# ioboard.net
KiCad netlist of a schematic drawn in EAGLE
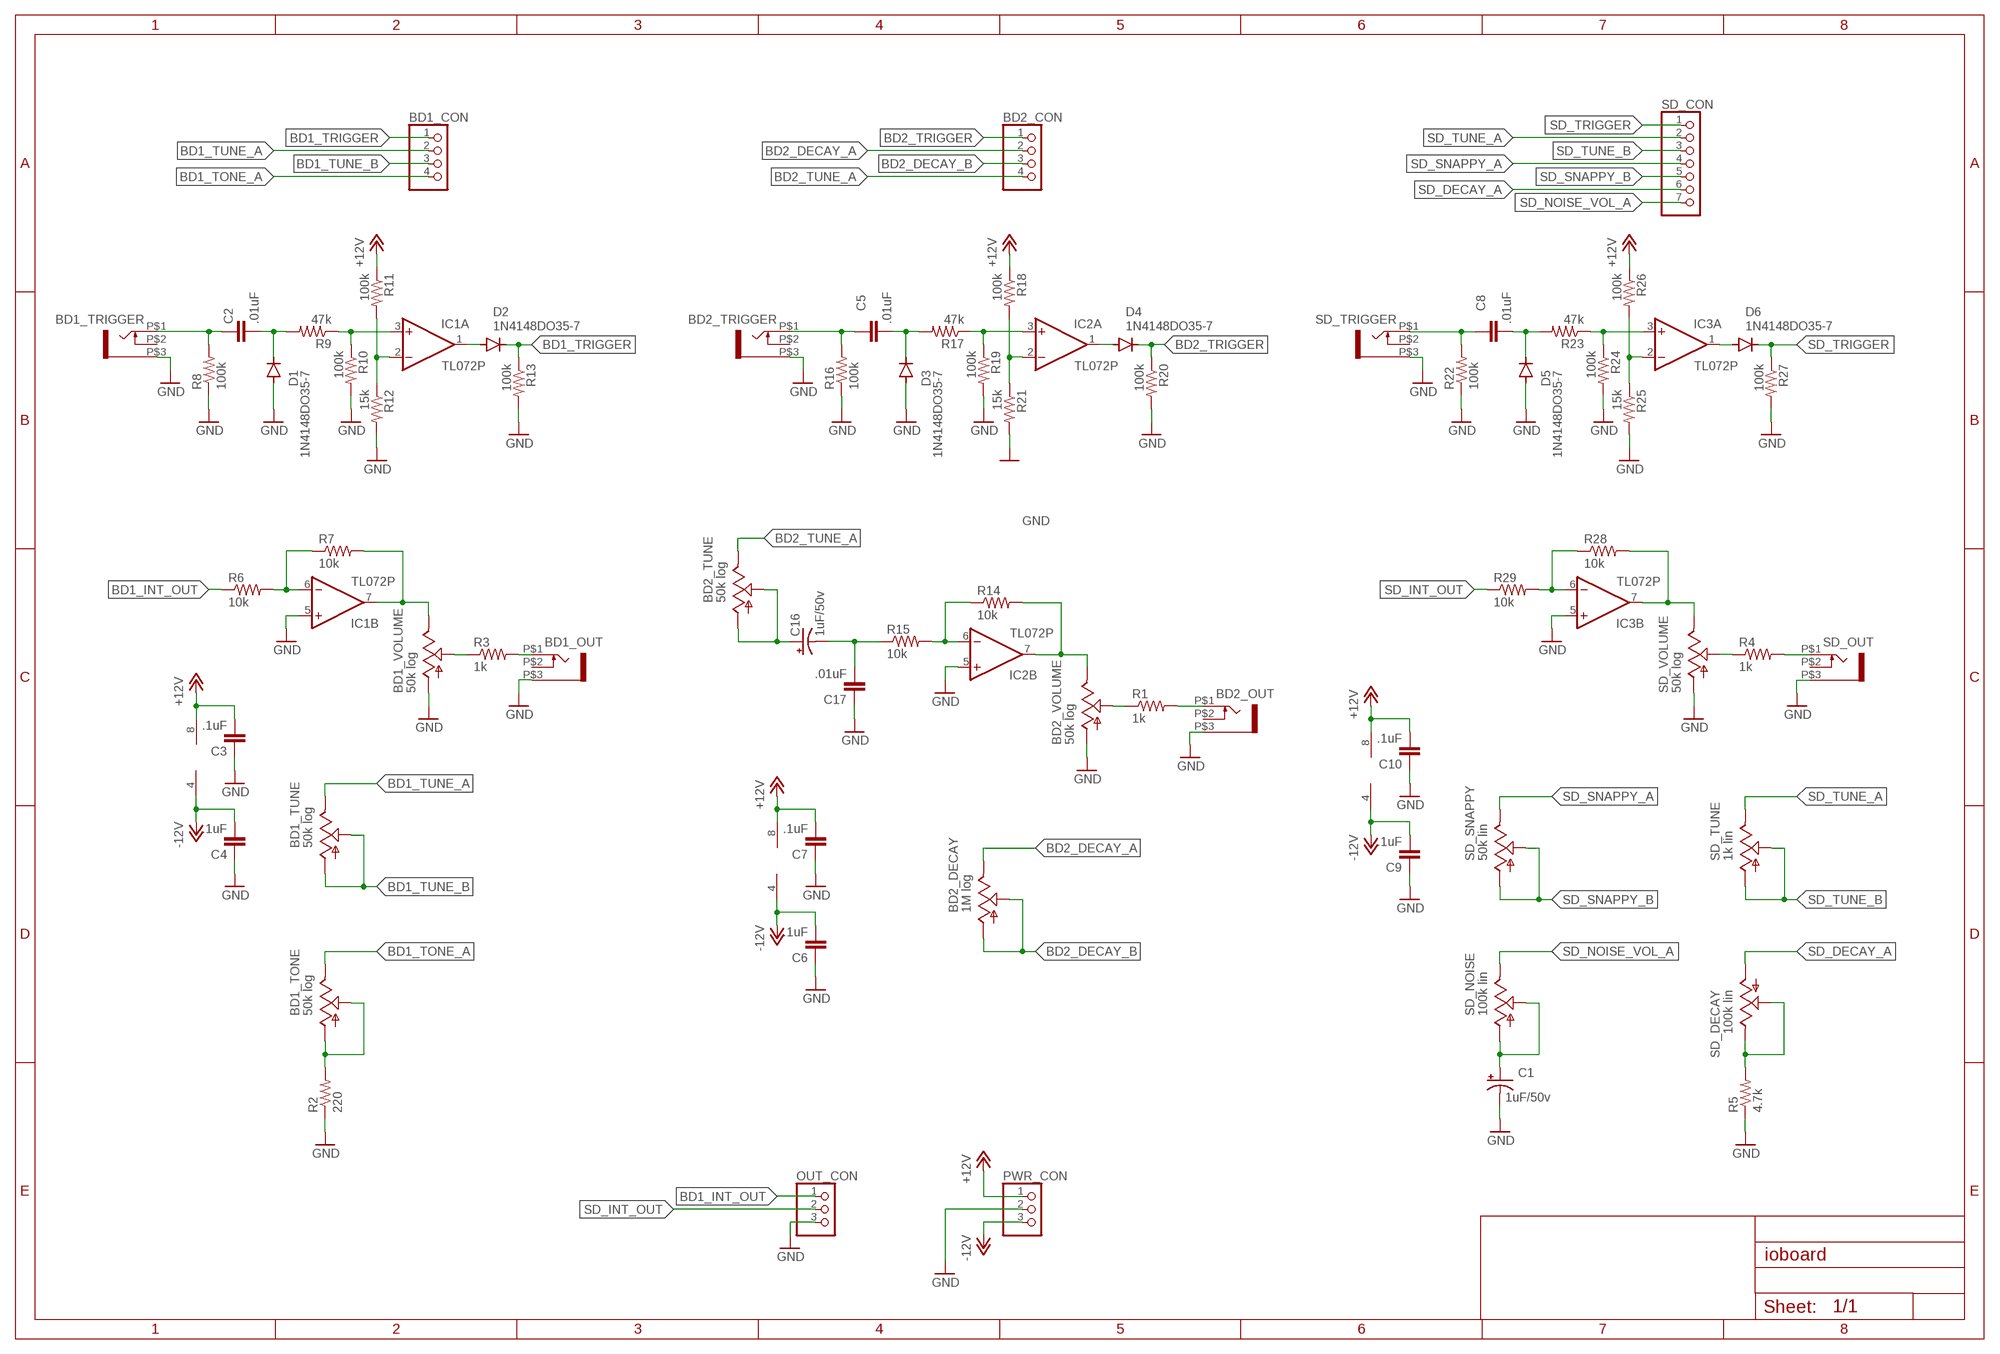
[diagram p0: schematic, sheet 1]

(export (version "E")
  (design (tool "Eeschema 10.0.6"))
  (components
    (comp (ref "BD1_CON")
      (value "PINHD-1X4")
      (footprint "eagle-import:1X04")
      (libsource (lib "eagle-import") (part "PINHD-1X4"))
    )
    (comp (ref "BD1_OUT")
      (value "WQP-PJ301M-12_JACK")
      (footprint "eagle-import:WQP-PJ301M-12_JACK")
      (libsource (lib "eagle-import") (part "WQP-PJ301M-12_JACK"))
    )
    (comp (ref "BD1_TONE")
      (value "50k log")
      (footprint "eagle-import:EVUF")
      (libsource (lib "eagle-import") (part "ALPHA-9MMA"))
    )
    (comp (ref "BD1_TRIGGER")
      (value "WQP-PJ301M-12_JACK")
      (footprint "eagle-import:WQP-PJ301M-12_JACK")
      (libsource (lib "eagle-import") (part "WQP-PJ301M-12_JACK"))
    )
    (comp (ref "BD1_TUNE")
      (value "50k log")
      (footprint "eagle-import:EVUF")
      (libsource (lib "eagle-import") (part "ALPHA-9MMA"))
    )
    (comp (ref "BD1_VOLUME")
      (value "50k log")
      (footprint "eagle-import:EVUF")
      (libsource (lib "eagle-import") (part "ALPHA-9MMA"))
    )
    (comp (ref "BD2_CON")
      (value "PINHD-1X4")
      (footprint "eagle-import:1X04")
      (libsource (lib "eagle-import") (part "PINHD-1X4"))
    )
    (comp (ref "BD2_DECAY")
      (value "1M log")
      (footprint "eagle-import:EVUF")
      (libsource (lib "eagle-import") (part "ALPHA-9MMA"))
    )
    (comp (ref "BD2_OUT")
      (value "WQP-PJ301M-12_JACK")
      (footprint "eagle-import:WQP-PJ301M-12_JACK")
      (libsource (lib "eagle-import") (part "WQP-PJ301M-12_JACK"))
    )
    (comp (ref "BD2_TRIGGER")
      (value "WQP-PJ301M-12_JACK")
      (footprint "eagle-import:WQP-PJ301M-12_JACK")
      (libsource (lib "eagle-import") (part "WQP-PJ301M-12_JACK"))
    )
    (comp (ref "BD2_TUNE")
      (value "50k log")
      (footprint "eagle-import:EVUF")
      (libsource (lib "eagle-import") (part "ALPHA-9MMA"))
    )
    (comp (ref "BD2_VOLUME")
      (value "50k log")
      (footprint "eagle-import:EVUF")
      (libsource (lib "eagle-import") (part "ALPHA-9MMA"))
    )
    (comp (ref "C1")
      (value "1uF/50v")
      (footprint "eagle-import:E2,5-5")
      (libsource (lib "eagle-import") (part "CPOL-USE2.5-5"))
    )
    (comp (ref "C2")
      (value ".01uF")
      (footprint "eagle-import:C050-024X044")
      (libsource (lib "eagle-import") (part "C-EU050-024X044"))
    )
    (comp (ref "C3")
      (value ".1uF")
      (footprint "eagle-import:C050-024X044")
      (libsource (lib "eagle-import") (part "C-EU050-024X044"))
    )
    (comp (ref "C4")
      (value ".1uF")
      (footprint "eagle-import:C050-024X044")
      (libsource (lib "eagle-import") (part "C-EU050-024X044"))
    )
    (comp (ref "C5")
      (value ".01uF")
      (footprint "eagle-import:C050-024X044")
      (libsource (lib "eagle-import") (part "C-EU050-024X044"))
    )
    (comp (ref "C6")
      (value ".1uF")
      (footprint "eagle-import:C050-024X044")
      (libsource (lib "eagle-import") (part "C-EU050-024X044"))
    )
    (comp (ref "C7")
      (value ".1uF")
      (footprint "eagle-import:C050-024X044")
      (libsource (lib "eagle-import") (part "C-EU050-024X044"))
    )
    (comp (ref "C8")
      (value ".01uF")
      (footprint "eagle-import:C050-024X044")
      (libsource (lib "eagle-import") (part "C-EU050-024X044"))
    )
    (comp (ref "C9")
      (value ".1uF")
      (footprint "eagle-import:C050-024X044")
      (libsource (lib "eagle-import") (part "C-EU050-024X044"))
    )
    (comp (ref "C10")
      (value ".1uF")
      (footprint "eagle-import:C050-024X044")
      (libsource (lib "eagle-import") (part "C-EU050-024X044"))
    )
    (comp (ref "C16")
      (value "1uF/50v")
      (footprint "eagle-import:E2,5-6")
      (libsource (lib "eagle-import") (part "CPOL-USE2.5-6"))
    )
    (comp (ref "C17")
      (value ".01uF")
      (footprint "eagle-import:C050-024X044")
      (libsource (lib "eagle-import") (part "resistor_C-EU050-024X044"))
    )
    (comp (ref "D1")
      (value "1N4148DO35-7")
      (footprint "eagle-import:DO35-7")
      (libsource (lib "eagle-import") (part "1N4148DO35-7"))
    )
    (comp (ref "D2")
      (value "1N4148DO35-7")
      (footprint "eagle-import:DO35-7")
      (libsource (lib "eagle-import") (part "1N4148DO35-7"))
    )
    (comp (ref "D3")
      (value "1N4148DO35-7")
      (footprint "eagle-import:DO35-7")
      (libsource (lib "eagle-import") (part "1N4148DO35-7"))
    )
    (comp (ref "D4")
      (value "1N4148DO35-7")
      (footprint "eagle-import:DO35-7")
      (libsource (lib "eagle-import") (part "1N4148DO35-7"))
    )
    (comp (ref "D5")
      (value "1N4148DO35-7")
      (footprint "eagle-import:DO35-7")
      (libsource (lib "eagle-import") (part "1N4148DO35-7"))
    )
    (comp (ref "D6")
      (value "1N4148DO35-7")
      (footprint "eagle-import:DO35-7")
      (libsource (lib "eagle-import") (part "1N4148DO35-7"))
    )
    (comp (ref "IC1")
      (value "TL072P")
      (footprint "eagle-import:DIL08")
      (libsource (lib "eagle-import") (part "TL072P"))
    )
    (comp (ref "IC2")
      (value "TL072P")
      (footprint "eagle-import:DIL08")
      (libsource (lib "eagle-import") (part "TL072P"))
    )
    (comp (ref "IC3")
      (value "TL072P")
      (footprint "eagle-import:DIL08")
      (libsource (lib "eagle-import") (part "TL072P"))
    )
    (comp (ref "OUT_CON")
      (value "PINHD-1X3")
      (footprint "eagle-import:1X03")
      (libsource (lib "eagle-import") (part "PINHD-1X3"))
    )
    (comp (ref "PWR_CON")
      (value "PINHD-1X3")
      (footprint "eagle-import:1X03")
      (libsource (lib "eagle-import") (part "PINHD-1X3"))
    )
    (comp (ref "R1")
      (value "1k")
      (footprint "eagle-import:0207_7")
      (libsource (lib "eagle-import") (part "R-US_0207/7"))
    )
    (comp (ref "R2")
      (value "220")
      (footprint "eagle-import:0207_7")
      (libsource (lib "eagle-import") (part "R-US_0207/7"))
    )
    (comp (ref "R3")
      (value "1k")
      (footprint "eagle-import:0207_7")
      (libsource (lib "eagle-import") (part "R-US_0207/7"))
    )
    (comp (ref "R4")
      (value "1k")
      (footprint "eagle-import:0207_7")
      (libsource (lib "eagle-import") (part "R-US_0207/7"))
    )
    (comp (ref "R5")
      (value "4.7k")
      (footprint "eagle-import:0207_7")
      (libsource (lib "eagle-import") (part "R-US_0207/7"))
    )
    (comp (ref "R6")
      (value "10k")
      (footprint "eagle-import:0207_7")
      (libsource (lib "eagle-import") (part "R-US_0207/7"))
    )
    (comp (ref "R7")
      (value "10k")
      (footprint "eagle-import:0207_7")
      (libsource (lib "eagle-import") (part "R-US_0207/7"))
    )
    (comp (ref "R8")
      (value "100k")
      (footprint "eagle-import:0207_7")
      (libsource (lib "eagle-import") (part "R-US_0207/7"))
    )
    (comp (ref "R9")
      (value "47k")
      (footprint "eagle-import:0207_7")
      (libsource (lib "eagle-import") (part "R-US_0207/7"))
    )
    (comp (ref "R10")
      (value "100k")
      (footprint "eagle-import:0207_7")
      (libsource (lib "eagle-import") (part "R-US_0207/7"))
    )
    (comp (ref "R11")
      (value "100k")
      (footprint "eagle-import:0207_7")
      (libsource (lib "eagle-import") (part "R-US_0207/7"))
    )
    (comp (ref "R12")
      (value "15k")
      (footprint "eagle-import:0207_7")
      (libsource (lib "eagle-import") (part "R-US_0207/7"))
    )
    (comp (ref "R13")
      (value "100k")
      (footprint "eagle-import:0207_7")
      (libsource (lib "eagle-import") (part "R-US_0207/7"))
    )
    (comp (ref "R14")
      (value "10k")
      (footprint "eagle-import:0207_7")
      (libsource (lib "eagle-import") (part "R-US_0207/7"))
    )
    (comp (ref "R15")
      (value "10k")
      (footprint "eagle-import:0207_7")
      (libsource (lib "eagle-import") (part "R-US_0207/7"))
    )
    (comp (ref "R16")
      (value "100k")
      (footprint "eagle-import:0207_7")
      (libsource (lib "eagle-import") (part "R-US_0207/7"))
    )
    (comp (ref "R17")
      (value "47k")
      (footprint "eagle-import:0207_7")
      (libsource (lib "eagle-import") (part "R-US_0207/7"))
    )
    (comp (ref "R18")
      (value "100k")
      (footprint "eagle-import:0207_7")
      (libsource (lib "eagle-import") (part "R-US_0207/7"))
    )
    (comp (ref "R19")
      (value "100k")
      (footprint "eagle-import:0207_7")
      (libsource (lib "eagle-import") (part "R-US_0207/7"))
    )
    (comp (ref "R20")
      (value "100k")
      (footprint "eagle-import:0207_7")
      (libsource (lib "eagle-import") (part "R-US_0207/7"))
    )
    (comp (ref "R21")
      (value "15k")
      (footprint "eagle-import:0207_7")
      (libsource (lib "eagle-import") (part "R-US_0207/7"))
    )
    (comp (ref "R22")
      (value "100k")
      (footprint "eagle-import:0207_7")
      (libsource (lib "eagle-import") (part "R-US_0207/7"))
    )
    (comp (ref "R23")
      (value "47k")
      (footprint "eagle-import:0207_7")
      (libsource (lib "eagle-import") (part "R-US_0207/7"))
    )
    (comp (ref "R24")
      (value "100k")
      (footprint "eagle-import:0207_7")
      (libsource (lib "eagle-import") (part "R-US_0207/7"))
    )
    (comp (ref "R25")
      (value "15k")
      (footprint "eagle-import:0207_7")
      (libsource (lib "eagle-import") (part "R-US_0207/7"))
    )
    (comp (ref "R26")
      (value "100k")
      (footprint "eagle-import:0207_7")
      (libsource (lib "eagle-import") (part "R-US_0207/7"))
    )
    (comp (ref "R27")
      (value "100k")
      (footprint "eagle-import:0207_7")
      (libsource (lib "eagle-import") (part "R-US_0207/7"))
    )
    (comp (ref "R28")
      (value "10k")
      (footprint "eagle-import:0207_7")
      (libsource (lib "eagle-import") (part "R-US_0207/7"))
    )
    (comp (ref "R29")
      (value "10k")
      (footprint "eagle-import:0207_7")
      (libsource (lib "eagle-import") (part "R-US_0207/7"))
    )
    (comp (ref "SD_CON")
      (value "PINHD-1X7")
      (footprint "eagle-import:1X07")
      (libsource (lib "eagle-import") (part "PINHD-1X7"))
    )
    (comp (ref "SD_DECAY")
      (value "100k lin")
      (footprint "eagle-import:EVUF")
      (libsource (lib "eagle-import") (part "ALPHA-9MMA"))
    )
    (comp (ref "SD_NOISE")
      (value "100k lin")
      (footprint "eagle-import:EVUF")
      (libsource (lib "eagle-import") (part "ALPHA-9MMA"))
    )
    (comp (ref "SD_OUT")
      (value "WQP-PJ301M-12_JACK")
      (footprint "eagle-import:WQP-PJ301M-12_JACK")
      (libsource (lib "eagle-import") (part "WQP-PJ301M-12_JACK"))
    )
    (comp (ref "SD_SNAPPY")
      (value "50k lin")
      (footprint "eagle-import:EVUF")
      (libsource (lib "eagle-import") (part "ALPHA-9MMA"))
    )
    (comp (ref "SD_TRIGGER")
      (value "WQP-PJ301M-12_JACK")
      (footprint "eagle-import:WQP-PJ301M-12_JACK")
      (libsource (lib "eagle-import") (part "WQP-PJ301M-12_JACK"))
    )
    (comp (ref "SD_TUNE")
      (value "1k lin")
      (footprint "eagle-import:EVUF")
      (libsource (lib "eagle-import") (part "ALPHA-9MMA"))
    )
    (comp (ref "SD_VOLUME")
      (value "50k log")
      (footprint "eagle-import:EVUF")
      (libsource (lib "eagle-import") (part "ALPHA-9MMA"))
    )
  )
  (nets
    (net (code "1") (name "+12V") (class "Default")
      (node (ref "C10") (pin "2") (pinfunction "2_2") (pintype "passive"))
      (node (ref "C3") (pin "2") (pinfunction "2_2") (pintype "passive"))
      (node (ref "C7") (pin "2") (pinfunction "2_2") (pintype "passive"))
      (node (ref "IC1") (pin "8") (pinfunction "V+_8") (pintype "power_in"))
      (node (ref "IC2") (pin "8") (pinfunction "V+_8") (pintype "power_in"))
      (node (ref "IC3") (pin "8") (pinfunction "V+_8") (pintype "power_in"))
      (node (ref "PWR_CON") (pin "1") (pinfunction "1_1") (pintype "passive"))
      (node (ref "R11") (pin "1") (pinfunction "1_1") (pintype "passive"))
      (node (ref "R18") (pin "1") (pinfunction "1_1") (pintype "passive"))
      (node (ref "R26") (pin "1") (pinfunction "1_1") (pintype "passive"))
    )
    (net (code "2") (name "-12V") (class "Default")
      (node (ref "C4") (pin "2") (pinfunction "2_2") (pintype "passive"))
      (node (ref "C6") (pin "2") (pinfunction "2_2") (pintype "passive"))
      (node (ref "C9") (pin "2") (pinfunction "2_2") (pintype "passive"))
      (node (ref "IC1") (pin "4") (pinfunction "V-_4") (pintype "power_in"))
      (node (ref "IC2") (pin "4") (pinfunction "V-_4") (pintype "power_in"))
      (node (ref "IC3") (pin "4") (pinfunction "V-_4") (pintype "power_in"))
      (node (ref "PWR_CON") (pin "3") (pinfunction "3_3") (pintype "passive"))
    )
    (net (code "3") (name "BD1_INT_OUT") (class "Default")
      (node (ref "OUT_CON") (pin "1") (pinfunction "1_1") (pintype "passive"))
      (node (ref "R6") (pin "1") (pinfunction "1_1") (pintype "passive"))
    )
    (net (code "4") (name "BD1_TONE_A") (class "Default")
      (node (ref "BD1_CON") (pin "4") (pinfunction "4_4") (pintype "passive"))
      (node (ref "BD1_TONE") (pin "3") (pinfunction "E_3") (pintype "passive"))
    )
    (net (code "5") (name "BD1_TRIGGER") (class "Default")
      (node (ref "BD1_CON") (pin "1") (pinfunction "1_1") (pintype "passive"))
      (node (ref "D2") (pin "C") (pinfunction "C_C") (pintype "passive"))
      (node (ref "R13") (pin "1") (pinfunction "1_1") (pintype "passive"))
    )
    (net (code "6") (name "BD1_TUNE_A") (class "Default")
      (node (ref "BD1_CON") (pin "2") (pinfunction "2_2") (pintype "passive"))
      (node (ref "BD1_TUNE") (pin "3") (pinfunction "E_3") (pintype "passive"))
    )
    (net (code "7") (name "BD1_TUNE_B") (class "Default")
      (node (ref "BD1_CON") (pin "3") (pinfunction "3_3") (pintype "passive"))
      (node (ref "BD1_TUNE") (pin "1") (pinfunction "A_1") (pintype "passive"))
      (node (ref "BD1_TUNE") (pin "2") (pinfunction "S_2") (pintype "passive"))
    )
    (net (code "8") (name "BD2_DECAY_A") (class "Default")
      (node (ref "BD2_CON") (pin "2") (pinfunction "2_2") (pintype "passive"))
      (node (ref "BD2_DECAY") (pin "3") (pinfunction "E_3") (pintype "passive"))
    )
    (net (code "9") (name "BD2_DECAY_B") (class "Default")
      (node (ref "BD2_CON") (pin "3") (pinfunction "3_3") (pintype "passive"))
      (node (ref "BD2_DECAY") (pin "1") (pinfunction "A_1") (pintype "passive"))
      (node (ref "BD2_DECAY") (pin "2") (pinfunction "S_2") (pintype "passive"))
    )
    (net (code "10") (name "BD2_TRIGGER") (class "Default")
      (node (ref "BD2_CON") (pin "1") (pinfunction "1_1") (pintype "passive"))
      (node (ref "D4") (pin "C") (pinfunction "C_C") (pintype "passive"))
      (node (ref "R20") (pin "1") (pinfunction "1_1") (pintype "passive"))
    )
    (net (code "11") (name "BD2_TUNE_A") (class "Default")
      (node (ref "BD2_CON") (pin "4") (pinfunction "4_4") (pintype "passive"))
      (node (ref "BD2_TUNE") (pin "3") (pinfunction "E_3") (pintype "passive"))
    )
    (net (code "12") (name "GND") (class "Default")
      (node (ref "BD1_OUT") (pin "P$3") (pinfunction "1_P$3") (pintype "passive"))
      (node (ref "BD1_TRIGGER") (pin "P$3") (pinfunction "1_P$3") (pintype "passive"))
      (node (ref "BD1_VOLUME") (pin "1") (pinfunction "A_1") (pintype "passive"))
      (node (ref "BD2_OUT") (pin "P$3") (pinfunction "1_P$3") (pintype "passive"))
      (node (ref "BD2_TRIGGER") (pin "P$3") (pinfunction "1_P$3") (pintype "passive"))
      (node (ref "BD2_VOLUME") (pin "1") (pinfunction "A_1") (pintype "passive"))
      (node (ref "C1") (pin "-") (pinfunction "-_-") (pintype "passive"))
      (node (ref "C10") (pin "1") (pinfunction "1_1") (pintype "passive"))
      (node (ref "C17") (pin "1") (pinfunction "1_1") (pintype "passive"))
      (node (ref "C3") (pin "1") (pinfunction "1_1") (pintype "passive"))
      (node (ref "C4") (pin "1") (pinfunction "1_1") (pintype "passive"))
      (node (ref "C6") (pin "1") (pinfunction "1_1") (pintype "passive"))
      (node (ref "C7") (pin "1") (pinfunction "1_1") (pintype "passive"))
      (node (ref "C9") (pin "1") (pinfunction "1_1") (pintype "passive"))
      (node (ref "D1") (pin "A") (pinfunction "A_A") (pintype "passive"))
      (node (ref "D3") (pin "A") (pinfunction "A_A") (pintype "passive"))
      (node (ref "D5") (pin "A") (pinfunction "A_A") (pintype "passive"))
      (node (ref "IC1") (pin "5") (pinfunction "+IN_5") (pintype "input"))
      (node (ref "IC2") (pin "5") (pinfunction "+IN_5") (pintype "input"))
      (node (ref "IC3") (pin "5") (pinfunction "+IN_5") (pintype "input"))
      (node (ref "OUT_CON") (pin "3") (pinfunction "3_3") (pintype "passive"))
      (node (ref "PWR_CON") (pin "2") (pinfunction "2_2") (pintype "passive"))
      (node (ref "R10") (pin "2") (pinfunction "2_2") (pintype "passive"))
      (node (ref "R12") (pin "2") (pinfunction "2_2") (pintype "passive"))
      (node (ref "R13") (pin "2") (pinfunction "2_2") (pintype "passive"))
      (node (ref "R16") (pin "1") (pinfunction "1_1") (pintype "passive"))
      (node (ref "R19") (pin "2") (pinfunction "2_2") (pintype "passive"))
      (node (ref "R2") (pin "1") (pinfunction "1_1") (pintype "passive"))
      (node (ref "R20") (pin "2") (pinfunction "2_2") (pintype "passive"))
      (node (ref "R21") (pin "2") (pinfunction "2_2") (pintype "passive"))
      (node (ref "R22") (pin "1") (pinfunction "1_1") (pintype "passive"))
      (node (ref "R24") (pin "2") (pinfunction "2_2") (pintype "passive"))
      (node (ref "R25") (pin "2") (pinfunction "2_2") (pintype "passive"))
      (node (ref "R27") (pin "2") (pinfunction "2_2") (pintype "passive"))
      (node (ref "R5") (pin "1") (pinfunction "1_1") (pintype "passive"))
      (node (ref "R8") (pin "1") (pinfunction "1_1") (pintype "passive"))
      (node (ref "SD_OUT") (pin "P$3") (pinfunction "1_P$3") (pintype "passive"))
      (node (ref "SD_TRIGGER") (pin "P$3") (pinfunction "1_P$3") (pintype "passive"))
      (node (ref "SD_VOLUME") (pin "1") (pinfunction "A_1") (pintype "passive"))
    )
    (net (code "13") (name "Net-(BD1_OUT-2)") (class "Default")
      (node (ref "BD1_OUT") (pin "P$1") (pinfunction "2_P$1") (pintype "passive"))
      (node (ref "R3") (pin "2") (pinfunction "2_2") (pintype "passive"))
    )
    (net (code "14") (name "Net-(BD1_TONE-A)") (class "Default")
      (node (ref "BD1_TONE") (pin "1") (pinfunction "A_1") (pintype "passive"))
      (node (ref "BD1_TONE") (pin "2") (pinfunction "S_2") (pintype "passive"))
      (node (ref "R2") (pin "2") (pinfunction "2_2") (pintype "passive"))
    )
    (net (code "15") (name "Net-(BD1_TRIGGER-2)") (class "Default")
      (node (ref "BD1_TRIGGER") (pin "P$1") (pinfunction "2_P$1") (pintype "passive"))
      (node (ref "C2") (pin "1") (pinfunction "1_1") (pintype "passive"))
      (node (ref "R8") (pin "2") (pinfunction "2_2") (pintype "passive"))
    )
    (net (code "16") (name "Net-(BD1_VOLUME-E)") (class "Default")
      (node (ref "BD1_VOLUME") (pin "3") (pinfunction "E_3") (pintype "passive"))
      (node (ref "IC1") (pin "7") (pinfunction "OUT_7") (pintype "output"))
      (node (ref "R7") (pin "2") (pinfunction "2_2") (pintype "passive"))
    )
    (net (code "17") (name "Net-(BD1_VOLUME-S)") (class "Default")
      (node (ref "BD1_VOLUME") (pin "2") (pinfunction "S_2") (pintype "passive"))
      (node (ref "R3") (pin "1") (pinfunction "1_1") (pintype "passive"))
    )
    (net (code "18") (name "Net-(BD2_OUT-2)") (class "Default")
      (node (ref "BD2_OUT") (pin "P$1") (pinfunction "2_P$1") (pintype "passive"))
      (node (ref "R1") (pin "2") (pinfunction "2_2") (pintype "passive"))
    )
    (net (code "19") (name "Net-(BD2_TRIGGER-2)") (class "Default")
      (node (ref "BD2_TRIGGER") (pin "P$1") (pinfunction "2_P$1") (pintype "passive"))
      (node (ref "C5") (pin "1") (pinfunction "1_1") (pintype "passive"))
      (node (ref "R16") (pin "2") (pinfunction "2_2") (pintype "passive"))
    )
    (net (code "20") (name "Net-(BD2_TUNE-A)") (class "Default")
      (node (ref "BD2_TUNE") (pin "1") (pinfunction "A_1") (pintype "passive"))
      (node (ref "BD2_TUNE") (pin "2") (pinfunction "S_2") (pintype "passive"))
      (node (ref "C16") (pin "+") (pinfunction "+_+") (pintype "passive"))
    )
    (net (code "21") (name "Net-(BD2_VOLUME-E)") (class "Default")
      (node (ref "BD2_VOLUME") (pin "3") (pinfunction "E_3") (pintype "passive"))
      (node (ref "IC2") (pin "7") (pinfunction "OUT_7") (pintype "output"))
      (node (ref "R14") (pin "2") (pinfunction "2_2") (pintype "passive"))
    )
    (net (code "22") (name "Net-(BD2_VOLUME-S)") (class "Default")
      (node (ref "BD2_VOLUME") (pin "2") (pinfunction "S_2") (pintype "passive"))
      (node (ref "R1") (pin "1") (pinfunction "1_1") (pintype "passive"))
    )
    (net (code "23") (name "Net-(C2-Pad2)") (class "Default")
      (node (ref "C2") (pin "2") (pinfunction "2_2") (pintype "passive"))
      (node (ref "D1") (pin "C") (pinfunction "C_C") (pintype "passive"))
      (node (ref "R9") (pin "2") (pinfunction "2_2") (pintype "passive"))
    )
    (net (code "24") (name "Net-(C5-Pad2)") (class "Default")
      (node (ref "C5") (pin "2") (pinfunction "2_2") (pintype "passive"))
      (node (ref "D3") (pin "C") (pinfunction "C_C") (pintype "passive"))
      (node (ref "R17") (pin "2") (pinfunction "2_2") (pintype "passive"))
    )
    (net (code "25") (name "Net-(C8-Pad2)") (class "Default")
      (node (ref "C8") (pin "2") (pinfunction "2_2") (pintype "passive"))
      (node (ref "D5") (pin "C") (pinfunction "C_C") (pintype "passive"))
      (node (ref "R23") (pin "2") (pinfunction "2_2") (pintype "passive"))
    )
    (net (code "26") (name "Net-(C16-Pad-)") (class "Default")
      (node (ref "C16") (pin "-") (pinfunction "-_-") (pintype "passive"))
      (node (ref "C17") (pin "2") (pinfunction "2_2") (pintype "passive"))
      (node (ref "R15") (pin "1") (pinfunction "1_1") (pintype "passive"))
    )
    (net (code "27") (name "Net-(IC1A-+IN)") (class "Default")
      (node (ref "IC1") (pin "3") (pinfunction "+IN_3") (pintype "input"))
      (node (ref "R10") (pin "1") (pinfunction "1_1") (pintype "passive"))
      (node (ref "R9") (pin "1") (pinfunction "1_1") (pintype "passive"))
    )
    (net (code "28") (name "Net-(IC1A--IN)") (class "Default")
      (node (ref "IC1") (pin "2") (pinfunction "-IN_2") (pintype "input"))
      (node (ref "R11") (pin "2") (pinfunction "2_2") (pintype "passive"))
      (node (ref "R12") (pin "1") (pinfunction "1_1") (pintype "passive"))
    )
    (net (code "29") (name "Net-(IC1A-OUT)") (class "Default")
      (node (ref "D2") (pin "A") (pinfunction "A_A") (pintype "passive"))
      (node (ref "IC1") (pin "1") (pinfunction "OUT_1") (pintype "output"))
    )
    (net (code "30") (name "Net-(IC1B--IN)") (class "Default")
      (node (ref "IC1") (pin "6") (pinfunction "-IN_6") (pintype "input"))
      (node (ref "R6") (pin "2") (pinfunction "2_2") (pintype "passive"))
      (node (ref "R7") (pin "1") (pinfunction "1_1") (pintype "passive"))
    )
    (net (code "31") (name "Net-(IC2A-+IN)") (class "Default")
      (node (ref "IC2") (pin "3") (pinfunction "+IN_3") (pintype "input"))
      (node (ref "R17") (pin "1") (pinfunction "1_1") (pintype "passive"))
      (node (ref "R19") (pin "1") (pinfunction "1_1") (pintype "passive"))
    )
    (net (code "32") (name "Net-(IC2A--IN)") (class "Default")
      (node (ref "IC2") (pin "2") (pinfunction "-IN_2") (pintype "input"))
      (node (ref "R18") (pin "2") (pinfunction "2_2") (pintype "passive"))
      (node (ref "R21") (pin "1") (pinfunction "1_1") (pintype "passive"))
    )
    (net (code "33") (name "Net-(IC2A-OUT)") (class "Default")
      (node (ref "D4") (pin "A") (pinfunction "A_A") (pintype "passive"))
      (node (ref "IC2") (pin "1") (pinfunction "OUT_1") (pintype "output"))
    )
    (net (code "34") (name "Net-(IC2B--IN)") (class "Default")
      (node (ref "IC2") (pin "6") (pinfunction "-IN_6") (pintype "input"))
      (node (ref "R14") (pin "1") (pinfunction "1_1") (pintype "passive"))
      (node (ref "R15") (pin "2") (pinfunction "2_2") (pintype "passive"))
    )
    (net (code "35") (name "Net-(IC3A-+IN)") (class "Default")
      (node (ref "IC3") (pin "3") (pinfunction "+IN_3") (pintype "input"))
      (node (ref "R23") (pin "1") (pinfunction "1_1") (pintype "passive"))
      (node (ref "R24") (pin "1") (pinfunction "1_1") (pintype "passive"))
    )
    (net (code "36") (name "Net-(IC3A--IN)") (class "Default")
      (node (ref "IC3") (pin "2") (pinfunction "-IN_2") (pintype "input"))
      (node (ref "R25") (pin "1") (pinfunction "1_1") (pintype "passive"))
      (node (ref "R26") (pin "2") (pinfunction "2_2") (pintype "passive"))
    )
    (net (code "37") (name "Net-(IC3A-OUT)") (class "Default")
      (node (ref "D6") (pin "A") (pinfunction "A_A") (pintype "passive"))
      (node (ref "IC3") (pin "1") (pinfunction "OUT_1") (pintype "output"))
    )
    (net (code "38") (name "Net-(IC3B--IN)") (class "Default")
      (node (ref "IC3") (pin "6") (pinfunction "-IN_6") (pintype "input"))
      (node (ref "R28") (pin "1") (pinfunction "1_1") (pintype "passive"))
      (node (ref "R29") (pin "2") (pinfunction "2_2") (pintype "passive"))
    )
    (net (code "39") (name "Net-(IC3B-OUT)") (class "Default")
      (node (ref "IC3") (pin "7") (pinfunction "OUT_7") (pintype "output"))
      (node (ref "R28") (pin "2") (pinfunction "2_2") (pintype "passive"))
      (node (ref "SD_VOLUME") (pin "3") (pinfunction "E_3") (pintype "passive"))
    )
    (net (code "40") (name "Net-(SD_DECAY-E)") (class "Default")
      (node (ref "R5") (pin "2") (pinfunction "2_2") (pintype "passive"))
      (node (ref "SD_DECAY") (pin "2") (pinfunction "S_2") (pintype "passive"))
      (node (ref "SD_DECAY") (pin "3") (pinfunction "E_3") (pintype "passive"))
    )
    (net (code "41") (name "Net-(SD_NOISE-A)") (class "Default")
      (node (ref "C1") (pin "+") (pinfunction "+_+") (pintype "passive"))
      (node (ref "SD_NOISE") (pin "1") (pinfunction "A_1") (pintype "passive"))
      (node (ref "SD_NOISE") (pin "2") (pinfunction "S_2") (pintype "passive"))
    )
    (net (code "42") (name "Net-(SD_OUT-2)") (class "Default")
      (node (ref "R4") (pin "2") (pinfunction "2_2") (pintype "passive"))
      (node (ref "SD_OUT") (pin "P$1") (pinfunction "2_P$1") (pintype "passive"))
    )
    (net (code "43") (name "Net-(SD_TRIGGER-2)") (class "Default")
      (node (ref "C8") (pin "1") (pinfunction "1_1") (pintype "passive"))
      (node (ref "R22") (pin "2") (pinfunction "2_2") (pintype "passive"))
      (node (ref "SD_TRIGGER") (pin "P$1") (pinfunction "2_P$1") (pintype "passive"))
    )
    (net (code "44") (name "Net-(SD_VOLUME-S)") (class "Default")
      (node (ref "R4") (pin "1") (pinfunction "1_1") (pintype "passive"))
      (node (ref "SD_VOLUME") (pin "2") (pinfunction "S_2") (pintype "passive"))
    )
    (net (code "45") (name "SD_DECAY_A") (class "Default")
      (node (ref "SD_CON") (pin "6") (pinfunction "6_6") (pintype "passive"))
      (node (ref "SD_DECAY") (pin "1") (pinfunction "A_1") (pintype "passive"))
    )
    (net (code "46") (name "SD_INT_OUT") (class "Default")
      (node (ref "OUT_CON") (pin "2") (pinfunction "2_2") (pintype "passive"))
      (node (ref "R29") (pin "1") (pinfunction "1_1") (pintype "passive"))
    )
    (net (code "47") (name "SD_NOISE_VOL_A") (class "Default")
      (node (ref "SD_CON") (pin "7") (pinfunction "7_7") (pintype "passive"))
      (node (ref "SD_NOISE") (pin "3") (pinfunction "E_3") (pintype "passive"))
    )
    (net (code "48") (name "SD_SNAPPY_A") (class "Default")
      (node (ref "SD_CON") (pin "4") (pinfunction "4_4") (pintype "passive"))
      (node (ref "SD_SNAPPY") (pin "3") (pinfunction "E_3") (pintype "passive"))
    )
    (net (code "49") (name "SD_SNAPPY_B") (class "Default")
      (node (ref "SD_CON") (pin "5") (pinfunction "5_5") (pintype "passive"))
      (node (ref "SD_SNAPPY") (pin "1") (pinfunction "A_1") (pintype "passive"))
      (node (ref "SD_SNAPPY") (pin "2") (pinfunction "S_2") (pintype "passive"))
    )
    (net (code "50") (name "SD_TRIGGER") (class "Default")
      (node (ref "D6") (pin "C") (pinfunction "C_C") (pintype "passive"))
      (node (ref "R27") (pin "1") (pinfunction "1_1") (pintype "passive"))
      (node (ref "SD_CON") (pin "1") (pinfunction "1_1") (pintype "passive"))
    )
    (net (code "51") (name "SD_TUNE_A") (class "Default")
      (node (ref "SD_CON") (pin "2") (pinfunction "2_2") (pintype "passive"))
      (node (ref "SD_TUNE") (pin "3") (pinfunction "E_3") (pintype "passive"))
    )
    (net (code "52") (name "SD_TUNE_B") (class "Default")
      (node (ref "SD_CON") (pin "3") (pinfunction "3_3") (pintype "passive"))
      (node (ref "SD_TUNE") (pin "1") (pinfunction "A_1") (pintype "passive"))
      (node (ref "SD_TUNE") (pin "2") (pinfunction "S_2") (pintype "passive"))
    )
    (net (code "53") (name "unconnected-(BD1_OUT-3-PadP$2)") (class "Default")
      (node (ref "BD1_OUT") (pin "P$2") (pinfunction "3_P$2") (pintype "passive"))
    )
    (net (code "54") (name "unconnected-(BD1_TRIGGER-3-PadP$2)") (class "Default")
      (node (ref "BD1_TRIGGER") (pin "P$2") (pinfunction "3_P$2") (pintype "passive"))
    )
    (net (code "55") (name "unconnected-(BD2_OUT-3-PadP$2)") (class "Default")
      (node (ref "BD2_OUT") (pin "P$2") (pinfunction "3_P$2") (pintype "passive"))
    )
    (net (code "56") (name "unconnected-(BD2_TRIGGER-3-PadP$2)") (class "Default")
      (node (ref "BD2_TRIGGER") (pin "P$2") (pinfunction "3_P$2") (pintype "passive"))
    )
    (net (code "57") (name "unconnected-(SD_OUT-3-PadP$2)") (class "Default")
      (node (ref "SD_OUT") (pin "P$2") (pinfunction "3_P$2") (pintype "passive"))
    )
    (net (code "58") (name "unconnected-(SD_TRIGGER-3-PadP$2)") (class "Default")
      (node (ref "SD_TRIGGER") (pin "P$2") (pinfunction "3_P$2") (pintype "passive"))
    )
  )
)
